# BSC0802BOB.net
KiCad netlist of a schematic drawn in Altium Designer
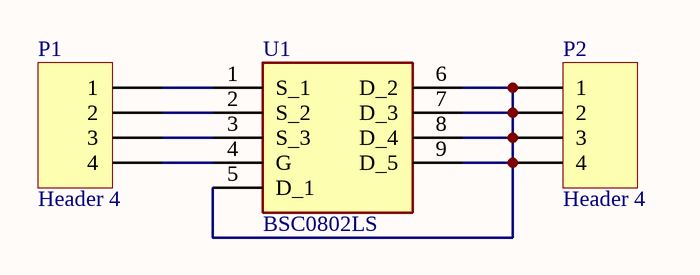
[diagram p0: BSC0802BOB.SchDoc]

(export (version "E")
  (design (tool "Eeschema 10.0.6"))
  (components
    (comp (ref "P1")
      (value "Header 4")
      (footprint "HDR1X4")
      (description "Header, 4-Pin")
      (fields (field (name "PUBLISHER") "Altium Limited"))
      (libsource (lib "Miscellaneous Connectors") (part "Header 4"))
    )
    (comp (ref "P2")
      (value "Header 4")
      (footprint "HDR1X4")
      (description "Header, 4-Pin")
      (fields (field (name "PUBLISHER") "Altium Limited"))
      (libsource (lib "") (part "Header 4_1"))
    )
    (comp (ref "U1")
      (value "BSC0802LS")
      (footprint "TDSON-8")
      (libsource (lib "RcMPPTLib") (part "BSC0802LS"))
    )
  )
  (nets
    (net (code "1") (name "Net-(U1-D_1)") (class "Default")
      (node (ref "P2") (pin "1") (pinfunction "1_1") (pintype "passive"))
      (node (ref "P2") (pin "2") (pinfunction "2_2") (pintype "passive"))
      (node (ref "P2") (pin "3") (pinfunction "3_3") (pintype "passive"))
      (node (ref "P2") (pin "4") (pinfunction "4_4") (pintype "passive"))
      (node (ref "U1") (pin "5") (pinfunction "D_1_5") (pintype "passive"))
      (node (ref "U1") (pin "6") (pinfunction "D_2_6") (pintype "passive"))
      (node (ref "U1") (pin "7") (pinfunction "D_3_7") (pintype "passive"))
      (node (ref "U1") (pin "8") (pinfunction "D_4_8") (pintype "passive"))
      (node (ref "U1") (pin "9") (pinfunction "D_5_9") (pintype "passive"))
    )
    (net (code "2") (name "Net-(U1-G)") (class "Default")
      (node (ref "P1") (pin "4") (pinfunction "4_4") (pintype "passive"))
      (node (ref "U1") (pin "4") (pinfunction "G_4") (pintype "passive"))
    )
    (net (code "3") (name "Net-(U1-S_1)") (class "Default")
      (node (ref "P1") (pin "1") (pinfunction "1_1") (pintype "passive"))
      (node (ref "U1") (pin "1") (pinfunction "S_1_1") (pintype "passive"))
    )
    (net (code "4") (name "Net-(U1-S_2)") (class "Default")
      (node (ref "P1") (pin "2") (pinfunction "2_2") (pintype "passive"))
      (node (ref "U1") (pin "2") (pinfunction "S_2_2") (pintype "passive"))
    )
    (net (code "5") (name "Net-(U1-S_3)") (class "Default")
      (node (ref "P1") (pin "3") (pinfunction "3_3") (pintype "passive"))
      (node (ref "U1") (pin "3") (pinfunction "S_3_3") (pintype "passive"))
    )
  )
)
